# SWD.net
KiCad netlist of a schematic drawn in Altium Designer
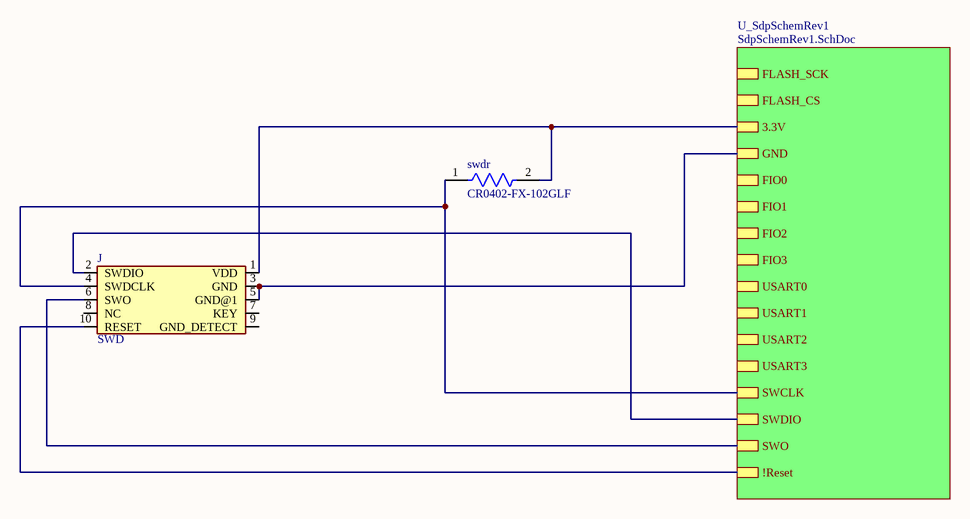
[diagram p0: SWD.SchDoc]

(export (version "E")
  (design (tool "Eeschema 10.0.6"))
  (components
    (comp (ref "J")
      (value "SWD")
      (footprint "2X10_BOXHEADER")
      (description "SWD WRITEON W/DISP .75X1.4 LAB")
      (fields (field (name "MF") "3M"))
      (libsource (lib "SWD") (part "SWD"))
    )
    (comp (ref "swdr")
      (value "CR0402-FX-102GLF")
      (footprint "FP-CR0402-IPC_C")
      (description "Thick Film Chip Resistors 0402 1kΩ 0.0625W 1% 100ppm/°C")
      (fields (field (name "TOLERANCE") "1%"))
      (libsource (lib "Altium Content Vault") (part "1029c3af85768c4190bb7ad29bc67b5"))
    )
  )
  (nets
    (net (code "1") (name "/!Reset") (class "Default")
      (node (ref "J") (pin "10") (pinfunction "RESET_10") (pintype "bidirectional"))
    )
    (net (code "2") (name "/3.3V") (class "Default")
      (node (ref "J") (pin "1") (pinfunction "VDD_1") (pintype "bidirectional"))
      (node (ref "swdr") (pin "2") (pinfunction "2_2") (pintype "passive"))
    )
    (net (code "9") (name "/GND") (class "Default")
      (node (ref "J") (pin "3") (pinfunction "GND_3") (pintype "bidirectional"))
      (node (ref "J") (pin "5") (pinfunction "GND@1_5") (pintype "bidirectional"))
    )
    (net (code "10") (name "/SWCLK") (class "Default")
      (node (ref "J") (pin "4") (pinfunction "SWDCLK_4") (pintype "bidirectional"))
      (node (ref "swdr") (pin "1") (pinfunction "1_1") (pintype "passive"))
    )
    (net (code "11") (name "/SWDIO") (class "Default")
      (node (ref "J") (pin "2") (pinfunction "SWDIO_2") (pintype "bidirectional"))
    )
    (net (code "12") (name "/SWO") (class "Default")
      (node (ref "J") (pin "6") (pinfunction "SWO_6") (pintype "bidirectional"))
    )
    (net (code "17") (name "unconnected-(J-GND_DETECT-Pad9)") (class "Default")
      (node (ref "J") (pin "9") (pinfunction "GND_DETECT_9") (pintype "bidirectional"))
    )
    (net (code "18") (name "unconnected-(J-KEY-Pad7)") (class "Default")
      (node (ref "J") (pin "7") (pinfunction "KEY_7") (pintype "bidirectional"))
    )
    (net (code "19") (name "unconnected-(J-NC-Pad8)") (class "Default")
      (node (ref "J") (pin "8") (pinfunction "NC_8") (pintype "bidirectional"))
    )
  )
)
